# CV_slew_limiter.net
KiCad netlist of a schematic drawn in EAGLE
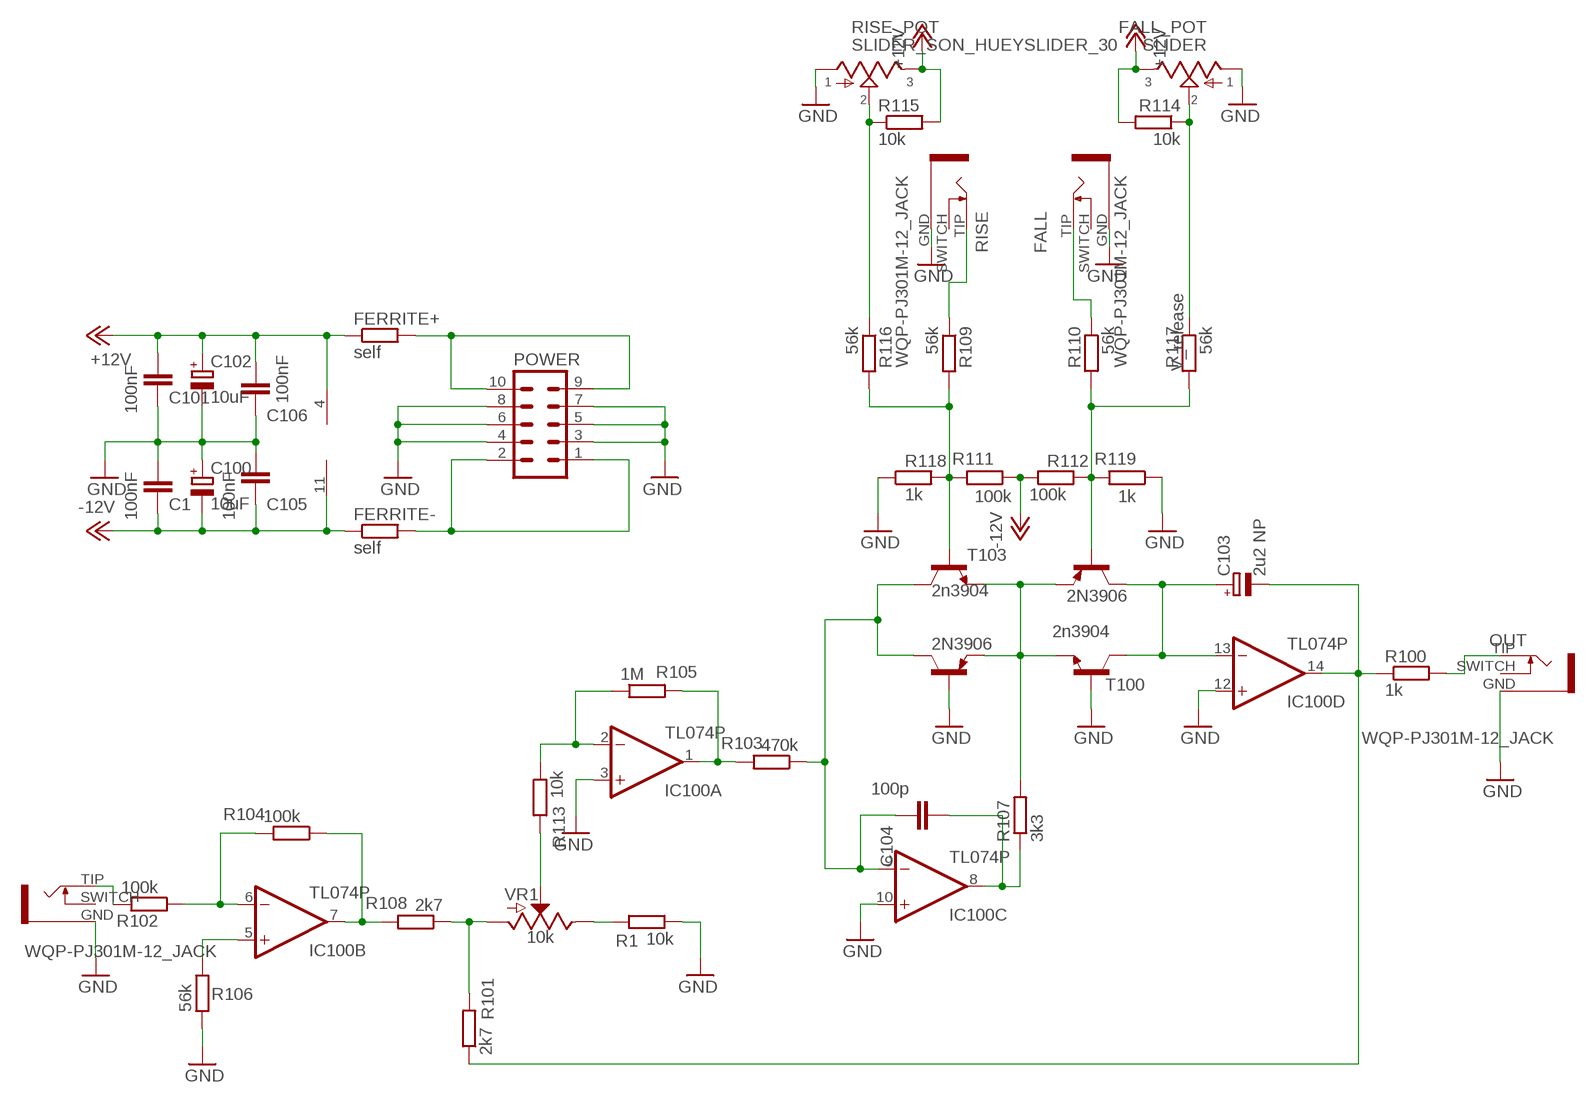
[diagram p0: schematic, sheet 1]

(export (version "E")
  (design (tool "Eeschema 10.0.6"))
  (components
    (comp (ref "C1")
      (value "100nF")
      (footprint "eagle-import:C050-025X075")
      (libsource (lib "eagle-import") (part "C-EU050-025X075"))
    )
    (comp (ref "C100")
      (value "10uF")
      (footprint "eagle-import:E2-4")
      (libsource (lib "eagle-import") (part "CPOL-EUE2-4"))
    )
    (comp (ref "C101")
      (value "100nF")
      (footprint "eagle-import:C050-025X075")
      (libsource (lib "eagle-import") (part "C-EU050-025X075"))
    )
    (comp (ref "C102")
      (value "10uF")
      (footprint "eagle-import:E2-4")
      (libsource (lib "eagle-import") (part "CPOL-EUE2-4"))
    )
    (comp (ref "C103")
      (value "2u2 NP")
      (footprint "eagle-import:E2-4")
      (libsource (lib "eagle-import") (part "CPOL-EUE2-4"))
    )
    (comp (ref "C104")
      (value "100p")
      (footprint "eagle-import:C050-025X075")
      (libsource (lib "eagle-import") (part "C-EU050-025X075"))
    )
    (comp (ref "C105")
      (value "100nF")
      (footprint "eagle-import:C050-025X075")
      (libsource (lib "eagle-import") (part "C-EU050-025X075"))
    )
    (comp (ref "C106")
      (value "100nF")
      (footprint "eagle-import:C050-025X075")
      (libsource (lib "eagle-import") (part "C-EU050-025X075"))
    )
    (comp (ref "FALL")
      (value "WQP-PJ301M-12_JACK")
      (footprint "eagle-import:WQP-PJ301M-12_JACK")
      (libsource (lib "eagle-import") (part "WQP-PJ301M-12_JACK"))
    )
    (comp (ref "FALL_POT")
      (value "SLIDER")
      (footprint "eagle-import:SILDER_30")
      (libsource (lib "eagle-import") (part "SLIDER_SON_HUEYSLIDER_30"))
    )
    (comp (ref "FERRITE+")
      (value "self")
      (footprint "eagle-import:0204_5")
      (libsource (lib "eagle-import") (part "R-EU_0204/5"))
    )
    (comp (ref "FERRITE-")
      (value "self")
      (footprint "eagle-import:0204_5")
      (libsource (lib "eagle-import") (part "R-EU_0204/5"))
    )
    (comp (ref "IC100")
      (value "TL074P")
      (footprint "eagle-import:DIL14")
      (libsource (lib "eagle-import") (part "TL074P"))
    )
    (comp (ref "IN")
      (value "WQP-PJ301M-12_JACK")
      (footprint "eagle-import:WQP-PJ301M-12_JACK")
      (libsource (lib "eagle-import") (part "WQP-PJ301M-12_JACK"))
    )
    (comp (ref "OUT")
      (value "WQP-PJ301M-12_JACK")
      (footprint "eagle-import:WQP-PJ301M-12_JACK")
      (libsource (lib "eagle-import") (part "WQP-PJ301M-12_JACK"))
    )
    (comp (ref "POWER")
      (value "ML10")
      (footprint "eagle-import:ML10")
      (fields (field (name "OC_FARNELL") "unknown") (field (name "OC_NEWARK") "unknown"))
      (libsource (lib "eagle-import") (part "ML10"))
    )
    (comp (ref "R1")
      (value "10k")
      (footprint "eagle-import:0204_5")
      (libsource (lib "eagle-import") (part "R-EU_0204/5"))
    )
    (comp (ref "R100")
      (value "1k")
      (footprint "eagle-import:0204_5")
      (libsource (lib "eagle-import") (part "R-EU_0204/5"))
    )
    (comp (ref "R101")
      (value "2k7")
      (footprint "eagle-import:0204_5")
      (libsource (lib "eagle-import") (part "R-EU_0204/5"))
    )
    (comp (ref "R102")
      (value "100k")
      (footprint "eagle-import:0204_5")
      (libsource (lib "eagle-import") (part "R-EU_0204/5"))
    )
    (comp (ref "R103")
      (value "470k")
      (footprint "eagle-import:0204_5")
      (libsource (lib "eagle-import") (part "R-EU_0204/5"))
    )
    (comp (ref "R104")
      (value "100k")
      (footprint "eagle-import:0204_5")
      (libsource (lib "eagle-import") (part "R-EU_0204/5"))
    )
    (comp (ref "R105")
      (value "1M")
      (footprint "eagle-import:0204_5")
      (libsource (lib "eagle-import") (part "R-EU_0204/5"))
    )
    (comp (ref "R106")
      (value "56k")
      (footprint "eagle-import:0204_5")
      (libsource (lib "eagle-import") (part "R-EU_0204/5"))
    )
    (comp (ref "R107")
      (value "3k3")
      (footprint "eagle-import:0204_5")
      (libsource (lib "eagle-import") (part "R-EU_0204/5"))
    )
    (comp (ref "R108")
      (value "2k7")
      (footprint "eagle-import:0204_5")
      (libsource (lib "eagle-import") (part "R-EU_0204/5"))
    )
    (comp (ref "R109")
      (value "56k")
      (footprint "eagle-import:0204_5")
      (libsource (lib "eagle-import") (part "R-EU_0204/5"))
    )
    (comp (ref "R110")
      (value "56k")
      (footprint "eagle-import:0204_5")
      (libsource (lib "eagle-import") (part "R-EU_0204/5"))
    )
    (comp (ref "R111")
      (value "100k")
      (footprint "eagle-import:0204_5")
      (libsource (lib "eagle-import") (part "R-EU_0204/5"))
    )
    (comp (ref "R112")
      (value "100k")
      (footprint "eagle-import:0204_5")
      (libsource (lib "eagle-import") (part "R-EU_0204/5"))
    )
    (comp (ref "R113")
      (value "10k")
      (footprint "eagle-import:0204_5")
      (libsource (lib "eagle-import") (part "R-EU_0204/5"))
    )
    (comp (ref "R114")
      (value "10k")
      (footprint "eagle-import:0204_5")
      (libsource (lib "eagle-import") (part "R-EU_0204/5"))
    )
    (comp (ref "R115")
      (value "10k")
      (footprint "eagle-import:0204_5")
      (libsource (lib "eagle-import") (part "R-EU_0204/5"))
    )
    (comp (ref "R116")
      (value "56k")
      (footprint "eagle-import:0204_5")
      (libsource (lib "eagle-import") (part "R-EU_0204/5"))
    )
    (comp (ref "R117")
      (value "56k")
      (footprint "eagle-import:0204_5")
      (libsource (lib "eagle-import") (part "R-EU_0204/5"))
    )
    (comp (ref "R118")
      (value "1k")
      (footprint "eagle-import:0204_5")
      (libsource (lib "eagle-import") (part "R-EU_0204/5"))
    )
    (comp (ref "R119")
      (value "1k")
      (footprint "eagle-import:0204_5")
      (libsource (lib "eagle-import") (part "R-EU_0204/5"))
    )
    (comp (ref "RISE")
      (value "WQP-PJ301M-12_JACK")
      (footprint "eagle-import:WQP-PJ301M-12_JACK")
      (libsource (lib "eagle-import") (part "WQP-PJ301M-12_JACK"))
    )
    (comp (ref "RISE_POT")
      (value "SLIDER_SON_HUEYSLIDER_30")
      (footprint "eagle-import:SILDER_30")
      (libsource (lib "eagle-import") (part "SLIDER_SON_HUEYSLIDER_30"))
    )
    (comp (ref "T100")
      (value "2n3904")
      (footprint "eagle-import:TO92-EBC")
      (libsource (lib "eagle-import") (part "-NPN-TO92-EBC2N3904"))
    )
    (comp (ref "T101")
      (value "2N3906")
      (footprint "eagle-import:TO92-EBC")
      (libsource (lib "eagle-import") (part "-PNP-TO92-EBC2N3906"))
    )
    (comp (ref "T102")
      (value "2N3906")
      (footprint "eagle-import:TO92-EBC")
      (libsource (lib "eagle-import") (part "-PNP-TO92-EBC2N3906"))
    )
    (comp (ref "T103")
      (value "2n3904")
      (footprint "eagle-import:TO92-EBC")
      (libsource (lib "eagle-import") (part "-NPN-TO92-EBC2N3904"))
    )
    (comp (ref "VR1")
      (value "10k")
      (footprint "eagle-import:POT-PTH-ALPS")
      (libsource (lib "eagle-import") (part "POTENTIOMETER-PTH-9MM-1/20W-20%"))
    )
  )
  (nets
    (net (code "1") (name "+12V") (class "Default")
      (node (ref "C101") (pin "2") (pinfunction "2_2") (pintype "passive"))
      (node (ref "C102") (pin "+") (pinfunction "+_+") (pintype "passive"))
      (node (ref "C106") (pin "2") (pinfunction "2_2") (pintype "passive"))
      (node (ref "FALL_POT") (pin "3") (pinfunction "3_3") (pintype "passive"))
      (node (ref "FERRITE+") (pin "1") (pinfunction "1_1") (pintype "passive"))
      (node (ref "IC100") (pin "4") (pinfunction "V+_4") (pintype "power_in"))
      (node (ref "R114") (pin "2") (pinfunction "2_2") (pintype "passive"))
      (node (ref "R115") (pin "2") (pinfunction "2_2") (pintype "passive"))
      (node (ref "RISE_POT") (pin "3") (pinfunction "3_3") (pintype "passive"))
    )
    (net (code "2") (name "-12V") (class "Default")
      (node (ref "C1") (pin "1") (pinfunction "1_1") (pintype "passive"))
      (node (ref "C100") (pin "-") (pinfunction "-_-") (pintype "passive"))
      (node (ref "C105") (pin "1") (pinfunction "1_1") (pintype "passive"))
      (node (ref "FERRITE-") (pin "1") (pinfunction "1_1") (pintype "passive"))
      (node (ref "IC100") (pin "11") (pinfunction "V-_11") (pintype "power_in"))
      (node (ref "R111") (pin "1") (pinfunction "1_1") (pintype "passive"))
      (node (ref "R112") (pin "1") (pinfunction "1_1") (pintype "passive"))
    )
    (net (code "3") (name "GND") (class "Default")
      (node (ref "C1") (pin "2") (pinfunction "2_2") (pintype "passive"))
      (node (ref "C100") (pin "+") (pinfunction "+_+") (pintype "passive"))
      (node (ref "C101") (pin "1") (pinfunction "1_1") (pintype "passive"))
      (node (ref "C102") (pin "-") (pinfunction "-_-") (pintype "passive"))
      (node (ref "C105") (pin "2") (pinfunction "2_2") (pintype "passive"))
      (node (ref "C106") (pin "1") (pinfunction "1_1") (pintype "passive"))
      (node (ref "FALL") (pin "GND") (pinfunction "1_GND") (pintype "passive"))
      (node (ref "FALL_POT") (pin "1") (pinfunction "1_1") (pintype "passive"))
      (node (ref "IC100") (pin "10") (pinfunction "+IN_10") (pintype "input"))
      (node (ref "IC100") (pin "12") (pinfunction "+IN_12") (pintype "input"))
      (node (ref "IC100") (pin "3") (pinfunction "+IN_3") (pintype "input"))
      (node (ref "IN") (pin "GND") (pinfunction "1_GND") (pintype "passive"))
      (node (ref "OUT") (pin "GND") (pinfunction "1_GND") (pintype "passive"))
      (node (ref "POWER") (pin "3") (pinfunction "3_3") (pintype "passive"))
      (node (ref "POWER") (pin "4") (pinfunction "4_4") (pintype "passive"))
      (node (ref "POWER") (pin "5") (pinfunction "5_5") (pintype "passive"))
      (node (ref "POWER") (pin "6") (pinfunction "6_6") (pintype "passive"))
      (node (ref "POWER") (pin "7") (pinfunction "7_7") (pintype "passive"))
      (node (ref "POWER") (pin "8") (pinfunction "8_8") (pintype "passive"))
      (node (ref "R1") (pin "1") (pinfunction "1_1") (pintype "passive"))
      (node (ref "R106") (pin "2") (pinfunction "2_2") (pintype "passive"))
      (node (ref "R118") (pin "1") (pinfunction "1_1") (pintype "passive"))
      (node (ref "R119") (pin "1") (pinfunction "1_1") (pintype "passive"))
      (node (ref "RISE") (pin "GND") (pinfunction "1_GND") (pintype "passive"))
      (node (ref "RISE_POT") (pin "1") (pinfunction "1_1") (pintype "passive"))
      (node (ref "T100") (pin "B") (pinfunction "B_B") (pintype "passive"))
      (node (ref "T102") (pin "B") (pinfunction "B_B") (pintype "passive"))
    )
    (net (code "4") (name "Net-(FALL-2)") (class "Default")
      (node (ref "FALL") (pin "TIP") (pinfunction "2_TIP") (pintype "passive"))
      (node (ref "R110") (pin "1") (pinfunction "1_1") (pintype "passive"))
    )
    (net (code "5") (name "Net-(FALL_POT-Pad2)") (class "Default")
      (node (ref "FALL_POT") (pin "2") (pinfunction "2_2") (pintype "passive"))
      (node (ref "R114") (pin "1") (pinfunction "1_1") (pintype "passive"))
      (node (ref "R117") (pin "1") (pinfunction "1_1") (pintype "passive"))
    )
    (net (code "6") (name "Net-(FERRITE+-Pad2)") (class "Default")
      (node (ref "FERRITE+") (pin "2") (pinfunction "2_2") (pintype "passive"))
      (node (ref "POWER") (pin "10") (pinfunction "10_10") (pintype "passive"))
      (node (ref "POWER") (pin "9") (pinfunction "9_9") (pintype "passive"))
    )
    (net (code "7") (name "Net-(FERRITE--Pad2)") (class "Default")
      (node (ref "FERRITE-") (pin "2") (pinfunction "2_2") (pintype "passive"))
      (node (ref "POWER") (pin "1") (pinfunction "1_1") (pintype "passive"))
      (node (ref "POWER") (pin "2") (pinfunction "2_2") (pintype "passive"))
    )
    (net (code "8") (name "Net-(IC100A--IN)") (class "Default")
      (node (ref "IC100") (pin "2") (pinfunction "-IN_2") (pintype "input"))
      (node (ref "R105") (pin "1") (pinfunction "1_1") (pintype "passive"))
      (node (ref "R113") (pin "1") (pinfunction "1_1") (pintype "passive"))
    )
    (net (code "9") (name "Net-(IC100A-OUT)") (class "Default")
      (node (ref "IC100") (pin "1") (pinfunction "OUT_1") (pintype "output"))
      (node (ref "R103") (pin "2") (pinfunction "2_2") (pintype "passive"))
      (node (ref "R105") (pin "2") (pinfunction "2_2") (pintype "passive"))
    )
    (net (code "10") (name "Net-(IC100B-+IN)") (class "Default")
      (node (ref "IC100") (pin "5") (pinfunction "+IN_5") (pintype "input"))
      (node (ref "R106") (pin "1") (pinfunction "1_1") (pintype "passive"))
    )
    (net (code "11") (name "Net-(IC100B--IN)") (class "Default")
      (node (ref "IC100") (pin "6") (pinfunction "-IN_6") (pintype "input"))
      (node (ref "R102") (pin "1") (pinfunction "1_1") (pintype "passive"))
      (node (ref "R104") (pin "2") (pinfunction "2_2") (pintype "passive"))
    )
    (net (code "12") (name "Net-(IC100B-OUT)") (class "Default")
      (node (ref "IC100") (pin "7") (pinfunction "OUT_7") (pintype "output"))
      (node (ref "R104") (pin "1") (pinfunction "1_1") (pintype "passive"))
      (node (ref "R108") (pin "2") (pinfunction "2_2") (pintype "passive"))
    )
    (net (code "13") (name "Net-(IC100C--IN)") (class "Default")
      (node (ref "C104") (pin "1") (pinfunction "1_1") (pintype "passive"))
      (node (ref "IC100") (pin "9") (pinfunction "-IN_9") (pintype "input"))
      (node (ref "R103") (pin "1") (pinfunction "1_1") (pintype "passive"))
      (node (ref "T102") (pin "C") (pinfunction "C_C") (pintype "passive"))
      (node (ref "T103") (pin "C") (pinfunction "C_C") (pintype "passive"))
    )
    (net (code "14") (name "Net-(IC100C-OUT)") (class "Default")
      (node (ref "C104") (pin "2") (pinfunction "2_2") (pintype "passive"))
      (node (ref "IC100") (pin "8") (pinfunction "OUT_8") (pintype "output"))
      (node (ref "R107") (pin "1") (pinfunction "1_1") (pintype "passive"))
    )
    (net (code "15") (name "Net-(IC100D--IN)") (class "Default")
      (node (ref "C103") (pin "+") (pinfunction "+_+") (pintype "passive"))
      (node (ref "IC100") (pin "13") (pinfunction "-IN_13") (pintype "input"))
      (node (ref "T100") (pin "C") (pinfunction "C_C") (pintype "passive"))
      (node (ref "T101") (pin "C") (pinfunction "C_C") (pintype "passive"))
    )
    (net (code "16") (name "Net-(IC100D-OUT)") (class "Default")
      (node (ref "C103") (pin "-") (pinfunction "-_-") (pintype "passive"))
      (node (ref "IC100") (pin "14") (pinfunction "OUT_14") (pintype "output"))
      (node (ref "R100") (pin "1") (pinfunction "1_1") (pintype "passive"))
      (node (ref "R101") (pin "1") (pinfunction "1_1") (pintype "passive"))
    )
    (net (code "17") (name "Net-(IN-2)") (class "Default")
      (node (ref "IN") (pin "TIP") (pinfunction "2_TIP") (pintype "passive"))
      (node (ref "R102") (pin "2") (pinfunction "2_2") (pintype "passive"))
    )
    (net (code "18") (name "Net-(OUT-2)") (class "Default")
      (node (ref "OUT") (pin "TIP") (pinfunction "2_TIP") (pintype "passive"))
      (node (ref "R100") (pin "2") (pinfunction "2_2") (pintype "passive"))
    )
    (net (code "19") (name "Net-(R107-Pad2)") (class "Default")
      (node (ref "R107") (pin "2") (pinfunction "2_2") (pintype "passive"))
      (node (ref "T100") (pin "E") (pinfunction "E_E") (pintype "passive"))
      (node (ref "T101") (pin "E") (pinfunction "E_E") (pintype "passive"))
      (node (ref "T102") (pin "E") (pinfunction "E_E") (pintype "passive"))
      (node (ref "T103") (pin "E") (pinfunction "E_E") (pintype "passive"))
    )
    (net (code "20") (name "Net-(R109-Pad2)") (class "Default")
      (node (ref "R109") (pin "2") (pinfunction "2_2") (pintype "passive"))
      (node (ref "R111") (pin "2") (pinfunction "2_2") (pintype "passive"))
      (node (ref "R116") (pin "2") (pinfunction "2_2") (pintype "passive"))
      (node (ref "R118") (pin "2") (pinfunction "2_2") (pintype "passive"))
      (node (ref "T103") (pin "B") (pinfunction "B_B") (pintype "passive"))
    )
    (net (code "21") (name "Net-(R110-Pad2)") (class "Default")
      (node (ref "R110") (pin "2") (pinfunction "2_2") (pintype "passive"))
      (node (ref "R112") (pin "2") (pinfunction "2_2") (pintype "passive"))
      (node (ref "R117") (pin "2") (pinfunction "2_2") (pintype "passive"))
      (node (ref "R119") (pin "2") (pinfunction "2_2") (pintype "passive"))
      (node (ref "T101") (pin "B") (pinfunction "B_B") (pintype "passive"))
    )
    (net (code "22") (name "Net-(R115-Pad1)") (class "Default")
      (node (ref "R115") (pin "1") (pinfunction "1_1") (pintype "passive"))
      (node (ref "R116") (pin "1") (pinfunction "1_1") (pintype "passive"))
      (node (ref "RISE_POT") (pin "2") (pinfunction "2_2") (pintype "passive"))
    )
    (net (code "23") (name "Net-(RISE-2)") (class "Default")
      (node (ref "R109") (pin "1") (pinfunction "1_1") (pintype "passive"))
      (node (ref "RISE") (pin "TIP") (pinfunction "2_TIP") (pintype "passive"))
    )
    (net (code "24") (name "Net-(VR1-A)") (class "Default")
      (node (ref "R101") (pin "2") (pinfunction "2_2") (pintype "passive"))
      (node (ref "R108") (pin "1") (pinfunction "1_1") (pintype "passive"))
      (node (ref "VR1") (pin "P$3") (pinfunction "A_P$3") (pintype "passive"))
    )
    (net (code "25") (name "Net-(VR1-E)") (class "Default")
      (node (ref "R1") (pin "2") (pinfunction "2_2") (pintype "passive"))
      (node (ref "VR1") (pin "P$1") (pinfunction "E_P$1") (pintype "passive"))
    )
    (net (code "26") (name "Net-(VR1-S)") (class "Default")
      (node (ref "R113") (pin "2") (pinfunction "2_2") (pintype "passive"))
      (node (ref "VR1") (pin "P$2") (pinfunction "S_P$2") (pintype "passive"))
    )
    (net (code "27") (name "unconnected-(FALL-3-PadSWITCH)") (class "Default")
      (node (ref "FALL") (pin "SWITCH") (pinfunction "3_SWITCH") (pintype "passive"))
    )
    (net (code "28") (name "unconnected-(IN-3-PadSWITCH)") (class "Default")
      (node (ref "IN") (pin "SWITCH") (pinfunction "3_SWITCH") (pintype "passive"))
    )
    (net (code "29") (name "unconnected-(OUT-3-PadSWITCH)") (class "Default")
      (node (ref "OUT") (pin "SWITCH") (pinfunction "3_SWITCH") (pintype "passive"))
    )
    (net (code "30") (name "unconnected-(RISE-3-PadSWITCH)") (class "Default")
      (node (ref "RISE") (pin "SWITCH") (pinfunction "3_SWITCH") (pintype "passive"))
    )
  )
)
